# RPi_Speaker.net
KiCad netlist of a schematic drawn in EAGLE
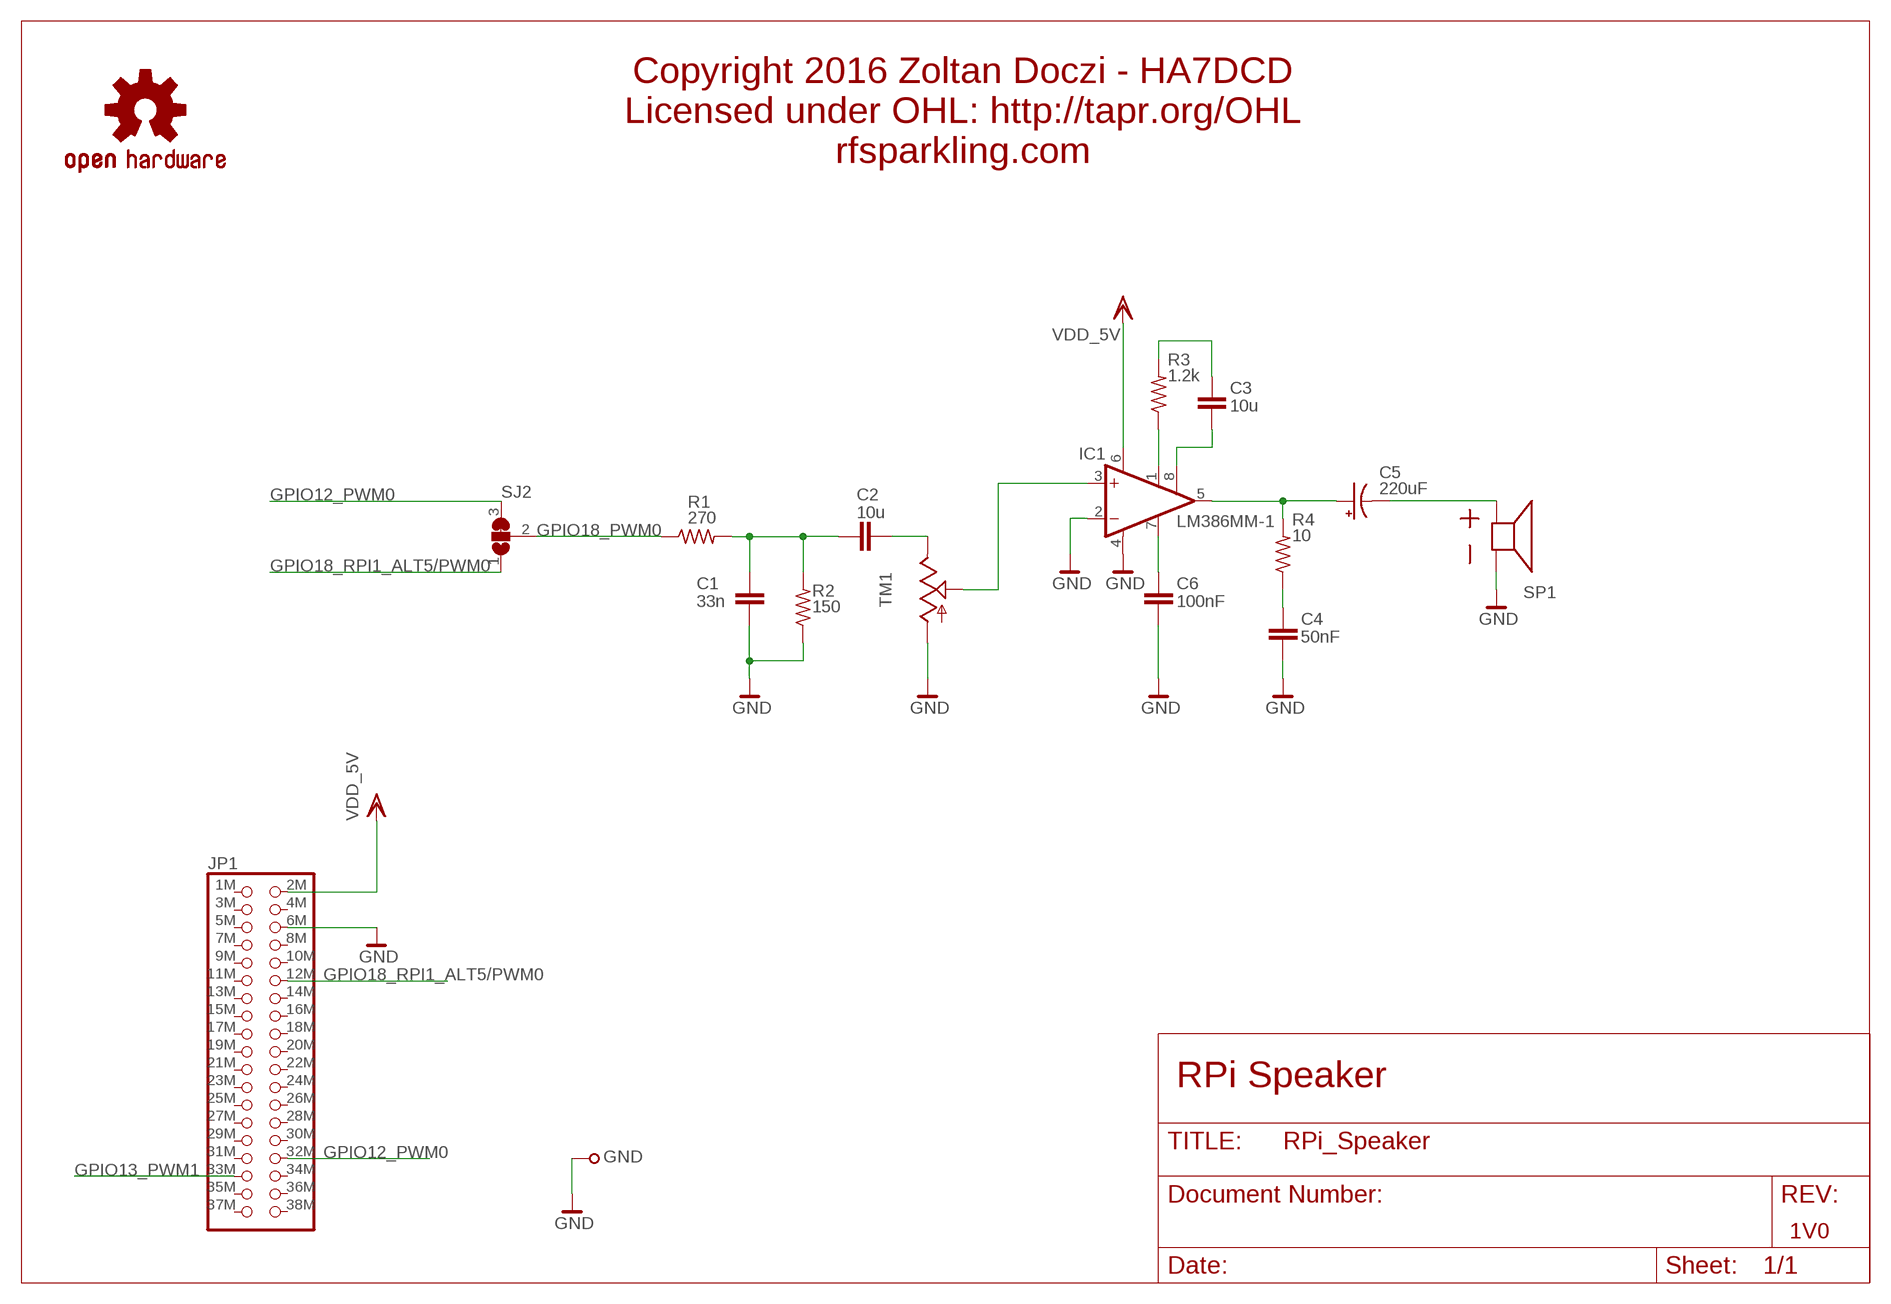
[diagram p0: schematic, sheet 1]

(export (version "E")
  (design (tool "Eeschema 10.0.6"))
  (components
    (comp (ref "C1")
      (value "33n")
      (footprint "eagle-import:0603")
      (libsource (lib "eagle-import") (part "CAP-SMD0603"))
    )
    (comp (ref "C2")
      (value "10u")
      (footprint "eagle-import:0603")
      (libsource (lib "eagle-import") (part "CAP-SMD0603"))
    )
    (comp (ref "C3")
      (value "10u")
      (footprint "eagle-import:0603")
      (libsource (lib "eagle-import") (part "CAP-SMD0603"))
    )
    (comp (ref "C4")
      (value "50nF")
      (footprint "eagle-import:0603")
      (libsource (lib "eagle-import") (part "CAP-SMD0603"))
    )
    (comp (ref "C5")
      (value "220uF")
      (footprint "eagle-import:D_7343-31R")
      (libsource (lib "eagle-import") (part "CPOL-USD/7343-31R"))
    )
    (comp (ref "C6")
      (value "100nF")
      (footprint "eagle-import:0603")
      (libsource (lib "eagle-import") (part "CAP-SMD0603"))
    )
    (comp (ref "GND")
      (value "TESTPOINT39MIL")
      (footprint "eagle-import:TESTPOINT1,0")
      (libsource (lib "eagle-import") (part "TESTPOINT39MIL"))
    )
    (comp (ref "IC1")
      (value "LM386MM-1")
      (footprint "eagle-import:MMSOP08")
      (libsource (lib "eagle-import") (part "LM386?-MM1"))
    )
    (comp (ref "JP1")
      (value "PINHD-2X18/MIRROR")
      (footprint "eagle-import:2X18_MIRROR")
      (libsource (lib "eagle-import") (part "PINHD-2X18/MIRROR"))
    )
    (comp (ref "R1")
      (value "270")
      (footprint "eagle-import:R0402")
      (libsource (lib "eagle-import") (part "R-US_R0402"))
    )
    (comp (ref "R2")
      (value "150")
      (footprint "eagle-import:R0402")
      (libsource (lib "eagle-import") (part "R-US_R0402"))
    )
    (comp (ref "R3")
      (value "1.2k")
      (footprint "eagle-import:R0402")
      (libsource (lib "eagle-import") (part "R-US_R0402"))
    )
    (comp (ref "R4")
      (value "10")
      (footprint "eagle-import:R0402")
      (libsource (lib "eagle-import") (part "R-US_R0402"))
    )
    (comp (ref "SJ2")
      (value "JUMPER_SMD_3A")
      (footprint "eagle-import:JUMPER_SMD_SJ2A")
      (libsource (lib "eagle-import") (part "JUMPER_SMD_3A"))
    )
    (comp (ref "SP1")
      (value "SPEAKER_ABS-210-RC")
      (footprint "eagle-import:SPEAKER_ABS-210-RC_50MM")
      (libsource (lib "eagle-import") (part "SPEAKER_ABS-210-RC"))
    )
    (comp (ref "TM1")
      (value "TRIM")
      (footprint "eagle-import:6MM")
      (libsource (lib "eagle-import") (part "TRIM"))
    )
    (comp (ref "U$15")
      (value "OSHW-LOGOS")
      (footprint "eagle-import:OSHW-LOGO-S")
      (libsource (lib "eagle-import") (part "OSHW-LOGOS"))
    )
  )
  (nets
    (net (code "1") (name "/GPIO12_PWM0") (class "Default")
      (node (ref "JP1") (pin "32M") (pinfunction "32_32M") (pintype "passive"))
      (node (ref "SJ2") (pin "3") (pinfunction "3_3") (pintype "passive"))
    )
    (net (code "2") (name "/GPIO13_PWM1") (class "Default")
      (node (ref "JP1") (pin "33M") (pinfunction "33_33M") (pintype "passive"))
    )
    (net (code "3") (name "/GPIO18_PWM0") (class "Default")
      (node (ref "R1") (pin "1") (pinfunction "1_1") (pintype "passive"))
      (node (ref "SJ2") (pin "2") (pinfunction "2_2") (pintype "passive"))
    )
    (net (code "4") (name "/GPIO18_RPI1_ALT5{slash}PWM0") (class "Default")
      (node (ref "JP1") (pin "12M") (pinfunction "12_12M") (pintype "passive"))
      (node (ref "SJ2") (pin "1") (pinfunction "1_1") (pintype "passive"))
    )
    (net (code "5") (name "GND") (class "Default")
      (node (ref "C1") (pin "1") (pinfunction "1_1") (pintype "passive"))
      (node (ref "C4") (pin "2") (pinfunction "2_2") (pintype "passive"))
      (node (ref "C6") (pin "2") (pinfunction "2_2") (pintype "passive"))
      (node (ref "GND") (pin "1") (pinfunction "P$1_1") (pintype "passive"))
      (node (ref "IC1") (pin "2") (pinfunction "-IN_2") (pintype "input"))
      (node (ref "IC1") (pin "4") (pinfunction "GND_4") (pintype "power_in"))
      (node (ref "JP1") (pin "6M") (pinfunction "6_6M") (pintype "passive"))
      (node (ref "R2") (pin "1") (pinfunction "1_1") (pintype "passive"))
      (node (ref "SP1") (pin "N") (pinfunction "-_N") (pintype "passive"))
      (node (ref "TM1") (pin "A") (pinfunction "A_A") (pintype "passive"))
    )
    (net (code "6") (name "Net-(C1-Pad2)") (class "Default")
      (node (ref "C1") (pin "2") (pinfunction "2_2") (pintype "passive"))
      (node (ref "C2") (pin "2") (pinfunction "2_2") (pintype "passive"))
      (node (ref "R1") (pin "2") (pinfunction "2_2") (pintype "passive"))
      (node (ref "R2") (pin "2") (pinfunction "2_2") (pintype "passive"))
    )
    (net (code "7") (name "Net-(C2-Pad1)") (class "Default")
      (node (ref "C2") (pin "1") (pinfunction "1_1") (pintype "passive"))
      (node (ref "TM1") (pin "E") (pinfunction "E_E") (pintype "passive"))
    )
    (net (code "8") (name "Net-(C3-Pad1)") (class "Default")
      (node (ref "C3") (pin "1") (pinfunction "1_1") (pintype "passive"))
      (node (ref "R3") (pin "2") (pinfunction "2_2") (pintype "passive"))
    )
    (net (code "9") (name "Net-(C3-Pad2)") (class "Default")
      (node (ref "C3") (pin "2") (pinfunction "2_2") (pintype "passive"))
      (node (ref "IC1") (pin "8") (pinfunction "GAIN_8") (pintype "passive"))
    )
    (net (code "10") (name "Net-(C4-Pad1)") (class "Default")
      (node (ref "C4") (pin "1") (pinfunction "1_1") (pintype "passive"))
      (node (ref "R4") (pin "1") (pinfunction "1_1") (pintype "passive"))
    )
    (net (code "11") (name "Net-(IC1-+IN)") (class "Default")
      (node (ref "IC1") (pin "3") (pinfunction "+IN_3") (pintype "input"))
      (node (ref "TM1") (pin "S") (pinfunction "S_S") (pintype "passive"))
    )
    (net (code "12") (name "Net-(IC1-BYPASS)") (class "Default")
      (node (ref "C6") (pin "1") (pinfunction "1_1") (pintype "passive"))
      (node (ref "IC1") (pin "7") (pinfunction "BYPASS_7") (pintype "passive"))
    )
    (net (code "13") (name "Net-(IC1-GAIN-Pad1)") (class "Default")
      (node (ref "IC1") (pin "1") (pinfunction "GAIN_1") (pintype "passive"))
      (node (ref "R3") (pin "1") (pinfunction "1_1") (pintype "passive"))
    )
    (net (code "14") (name "Net-(IC1-OUT)") (class "Default")
      (node (ref "C5") (pin "+") (pinfunction "+_+") (pintype "passive"))
      (node (ref "IC1") (pin "5") (pinfunction "OUT_5") (pintype "output"))
      (node (ref "R4") (pin "2") (pinfunction "2_2") (pintype "passive"))
    )
    (net (code "15") (name "Net-(SP1-+)") (class "Default")
      (node (ref "C5") (pin "-") (pinfunction "-_-") (pintype "passive"))
      (node (ref "SP1") (pin "P") (pinfunction "+_P") (pintype "passive"))
    )
    (net (code "16") (name "VDD_5V") (class "Default")
      (node (ref "IC1") (pin "6") (pinfunction "VS_6") (pintype "power_in"))
      (node (ref "JP1") (pin "2M") (pinfunction "2_2M") (pintype "passive"))
    )
    (net (code "17") (name "unconnected-(JP1-1-Pad1M)") (class "Default")
      (node (ref "JP1") (pin "1M") (pinfunction "1_1M") (pintype "passive"))
    )
    (net (code "18") (name "unconnected-(JP1-3-Pad3M)") (class "Default")
      (node (ref "JP1") (pin "3M") (pinfunction "3_3M") (pintype "passive"))
    )
    (net (code "19") (name "unconnected-(JP1-4-Pad4M)") (class "Default")
      (node (ref "JP1") (pin "4M") (pinfunction "4_4M") (pintype "passive"))
    )
    (net (code "20") (name "unconnected-(JP1-5-Pad5M)") (class "Default")
      (node (ref "JP1") (pin "5M") (pinfunction "5_5M") (pintype "passive"))
    )
    (net (code "21") (name "unconnected-(JP1-7-Pad7M)") (class "Default")
      (node (ref "JP1") (pin "7M") (pinfunction "7_7M") (pintype "passive"))
    )
    (net (code "22") (name "unconnected-(JP1-8-Pad8M)") (class "Default")
      (node (ref "JP1") (pin "8M") (pinfunction "8_8M") (pintype "passive"))
    )
    (net (code "23") (name "unconnected-(JP1-9-Pad9M)") (class "Default")
      (node (ref "JP1") (pin "9M") (pinfunction "9_9M") (pintype "passive"))
    )
    (net (code "24") (name "unconnected-(JP1-10-Pad10M)") (class "Default")
      (node (ref "JP1") (pin "10M") (pinfunction "10_10M") (pintype "passive"))
    )
    (net (code "25") (name "unconnected-(JP1-11-Pad11M)") (class "Default")
      (node (ref "JP1") (pin "11M") (pinfunction "11_11M") (pintype "passive"))
    )
    (net (code "26") (name "unconnected-(JP1-13-Pad13M)") (class "Default")
      (node (ref "JP1") (pin "13M") (pinfunction "13_13M") (pintype "passive"))
    )
    (net (code "27") (name "unconnected-(JP1-14-Pad14M)") (class "Default")
      (node (ref "JP1") (pin "14M") (pinfunction "14_14M") (pintype "passive"))
    )
    (net (code "28") (name "unconnected-(JP1-15-Pad15M)") (class "Default")
      (node (ref "JP1") (pin "15M") (pinfunction "15_15M") (pintype "passive"))
    )
    (net (code "29") (name "unconnected-(JP1-16-Pad16M)") (class "Default")
      (node (ref "JP1") (pin "16M") (pinfunction "16_16M") (pintype "passive"))
    )
    (net (code "30") (name "unconnected-(JP1-17-Pad17M)") (class "Default")
      (node (ref "JP1") (pin "17M") (pinfunction "17_17M") (pintype "passive"))
    )
    (net (code "31") (name "unconnected-(JP1-18-Pad18M)") (class "Default")
      (node (ref "JP1") (pin "18M") (pinfunction "18_18M") (pintype "passive"))
    )
    (net (code "32") (name "unconnected-(JP1-19-Pad19M)") (class "Default")
      (node (ref "JP1") (pin "19M") (pinfunction "19_19M") (pintype "passive"))
    )
    (net (code "33") (name "unconnected-(JP1-20-Pad20M)") (class "Default")
      (node (ref "JP1") (pin "20M") (pinfunction "20_20M") (pintype "passive"))
    )
    (net (code "34") (name "unconnected-(JP1-21-Pad21M)") (class "Default")
      (node (ref "JP1") (pin "21M") (pinfunction "21_21M") (pintype "passive"))
    )
    (net (code "35") (name "unconnected-(JP1-22-Pad22M)") (class "Default")
      (node (ref "JP1") (pin "22M") (pinfunction "22_22M") (pintype "passive"))
    )
    (net (code "36") (name "unconnected-(JP1-23-Pad23M)") (class "Default")
      (node (ref "JP1") (pin "23M") (pinfunction "23_23M") (pintype "passive"))
    )
    (net (code "37") (name "unconnected-(JP1-24-Pad24M)") (class "Default")
      (node (ref "JP1") (pin "24M") (pinfunction "24_24M") (pintype "passive"))
    )
    (net (code "38") (name "unconnected-(JP1-25-Pad25M)") (class "Default")
      (node (ref "JP1") (pin "25M") (pinfunction "25_25M") (pintype "passive"))
    )
    (net (code "39") (name "unconnected-(JP1-26-Pad26M)") (class "Default")
      (node (ref "JP1") (pin "26M") (pinfunction "26_26M") (pintype "passive"))
    )
    (net (code "40") (name "unconnected-(JP1-27-Pad27M)") (class "Default")
      (node (ref "JP1") (pin "27M") (pinfunction "27_27M") (pintype "passive"))
    )
    (net (code "41") (name "unconnected-(JP1-28-Pad28M)") (class "Default")
      (node (ref "JP1") (pin "28M") (pinfunction "28_28M") (pintype "passive"))
    )
    (net (code "42") (name "unconnected-(JP1-29-Pad29M)") (class "Default")
      (node (ref "JP1") (pin "29M") (pinfunction "29_29M") (pintype "passive"))
    )
    (net (code "43") (name "unconnected-(JP1-30-Pad30M)") (class "Default")
      (node (ref "JP1") (pin "30M") (pinfunction "30_30M") (pintype "passive"))
    )
    (net (code "44") (name "unconnected-(JP1-31-Pad31M)") (class "Default")
      (node (ref "JP1") (pin "31M") (pinfunction "31_31M") (pintype "passive"))
    )
    (net (code "45") (name "unconnected-(JP1-34-Pad34M)") (class "Default")
      (node (ref "JP1") (pin "34M") (pinfunction "34_34M") (pintype "passive"))
    )
    (net (code "46") (name "unconnected-(JP1-35-Pad35M)") (class "Default")
      (node (ref "JP1") (pin "35M") (pinfunction "35_35M") (pintype "passive"))
    )
    (net (code "47") (name "unconnected-(JP1-36-Pad36M)") (class "Default")
      (node (ref "JP1") (pin "36M") (pinfunction "36_36M") (pintype "passive"))
    )
    (net (code "48") (name "unconnected-(JP1-37-Pad37M)") (class "Default")
      (node (ref "JP1") (pin "37M") (pinfunction "37_37M") (pintype "passive"))
    )
    (net (code "49") (name "unconnected-(JP1-38-Pad38M)") (class "Default")
      (node (ref "JP1") (pin "38M") (pinfunction "38_38M") (pintype "passive"))
    )
  )
)
